# EC_mini_v31.net
KiCad netlist of a schematic drawn in EAGLE
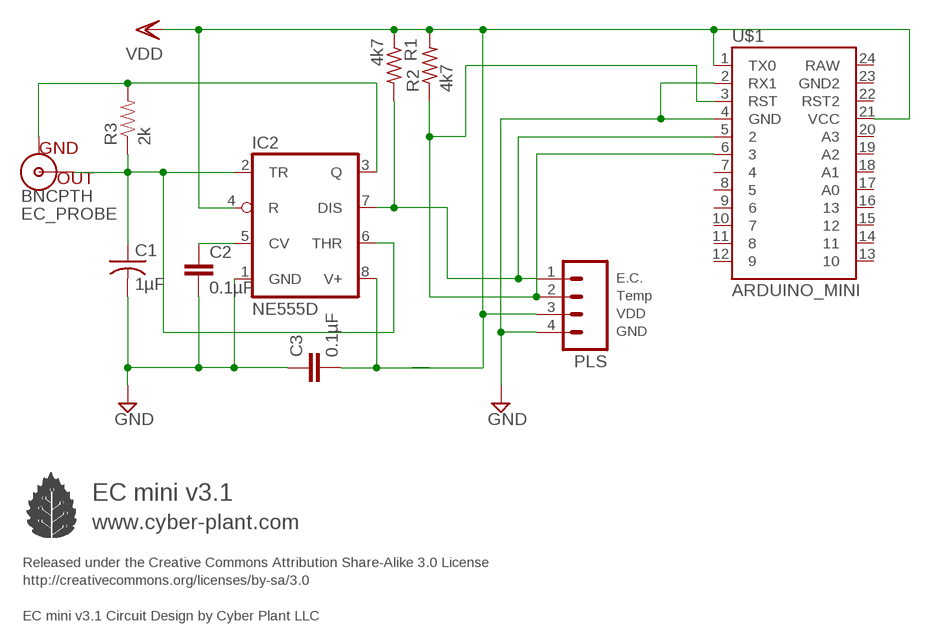
[diagram p0: schematic, sheet 1]

(export (version "E")
  (design (tool "Eeschema 10.0.6"))
  (components
    (comp (ref "C1")
      (value "1µF")
      (footprint "eagle-import:C050-045X075")
      (libsource (lib "eagle-import") (part "C-US050-045X075"))
    )
    (comp (ref "C2")
      (value "0.1µF")
      (footprint "eagle-import:1206")
      (libsource (lib "eagle-import") (part "CAP1206"))
    )
    (comp (ref "C3")
      (value "0.1µF")
      (footprint "eagle-import:1206")
      (libsource (lib "eagle-import") (part "CAP1206"))
    )
    (comp (ref "EC_PROBE")
      (value "BNCPTH")
      (footprint "eagle-import:BNC")
      (libsource (lib "eagle-import") (part "BNCPTH"))
    )
    (comp (ref "IC2")
      (value "NE555D")
      (footprint "eagle-import:SO08")
      (libsource (lib "eagle-import") (part "555DNE"))
    )
    (comp (ref "PLS")
      (value "M04PTH")
      (footprint "eagle-import:1X04")
      (libsource (lib "eagle-import") (part "M04PTH"))
    )
    (comp (ref "R1")
      (value "4k7")
      (footprint "eagle-import:0207_10")
      (libsource (lib "eagle-import") (part "R-US_0207/10"))
    )
    (comp (ref "R2")
      (value "4k7")
      (footprint "eagle-import:0207_10")
      (libsource (lib "eagle-import") (part "R-US_0207/10"))
    )
    (comp (ref "R3")
      (value "2k")
      (footprint "eagle-import:1206")
      (libsource (lib "eagle-import") (part "RESISTOR1206"))
    )
    (comp (ref "U$1")
      (value "ARDUINO_MINI")
      (footprint "eagle-import:ARDUINO_MINI")
      (libsource (lib "eagle-import") (part "ARDUINO_MINI"))
    )
  )
  (nets
    (net (code "1") (name "GND") (class "Default")
      (node (ref "C1") (pin "2") (pinfunction "2_2") (pintype "passive"))
      (node (ref "C2") (pin "2") (pinfunction "2_2") (pintype "passive"))
      (node (ref "C3") (pin "1") (pinfunction "1_1") (pintype "passive"))
      (node (ref "IC2") (pin "1") (pinfunction "GND_1") (pintype "power_in"))
      (node (ref "PLS") (pin "4") (pinfunction "4_4") (pintype "passive"))
      (node (ref "U$1") (pin "2") (pinfunction "RX1_2") (pintype "bidirectional"))
      (node (ref "U$1") (pin "4") (pinfunction "GND_4") (pintype "bidirectional"))
    )
    (net (code "2") (name "Net-(EC_PROBE-OUT)") (class "Default")
      (node (ref "C1") (pin "1") (pinfunction "1_1") (pintype "passive"))
      (node (ref "EC_PROBE") (pin "S") (pinfunction "OUT_S") (pintype "bidirectional"))
      (node (ref "IC2") (pin "2") (pinfunction "TR_2") (pintype "input"))
      (node (ref "IC2") (pin "6") (pinfunction "THR_6") (pintype "input"))
      (node (ref "R3") (pin "1") (pinfunction "1_1") (pintype "passive"))
    )
    (net (code "3") (name "Net-(IC2-CV)") (class "Default")
      (node (ref "C2") (pin "1") (pinfunction "1_1") (pintype "passive"))
      (node (ref "IC2") (pin "5") (pinfunction "CV_5") (pintype "input"))
    )
    (net (code "4") (name "Net-(IC2-DIS)") (class "Default")
      (node (ref "IC2") (pin "7") (pinfunction "DIS_7") (pintype "input"))
      (node (ref "PLS") (pin "1") (pinfunction "1_1") (pintype "passive"))
      (node (ref "R1") (pin "2") (pinfunction "2_2") (pintype "passive"))
      (node (ref "U$1") (pin "5") (pinfunction "2_5") (pintype "bidirectional"))
    )
    (net (code "5") (name "Net-(IC2-Q)") (class "Default")
      (node (ref "EC_PROBE") (pin "GND") (pinfunction "GND_GND") (pintype "bidirectional"))
      (node (ref "IC2") (pin "3") (pinfunction "Q_3") (pintype "output"))
      (node (ref "R3") (pin "2") (pinfunction "2_2") (pintype "passive"))
    )
    (net (code "6") (name "Net-(U$1-3)") (class "Default")
      (node (ref "PLS") (pin "2") (pinfunction "2_2") (pintype "passive"))
      (node (ref "R2") (pin "1") (pinfunction "1_1") (pintype "passive"))
      (node (ref "U$1") (pin "3") (pinfunction "RST_3") (pintype "bidirectional"))
      (node (ref "U$1") (pin "6") (pinfunction "3_6") (pintype "bidirectional"))
    )
    (net (code "7") (name "VDD") (class "Default")
      (node (ref "C3") (pin "2") (pinfunction "2_2") (pintype "passive"))
      (node (ref "IC2") (pin "4") (pinfunction "R_4") (pintype "input"))
      (node (ref "IC2") (pin "8") (pinfunction "V+_8") (pintype "power_in"))
      (node (ref "PLS") (pin "3") (pinfunction "3_3") (pintype "passive"))
      (node (ref "R1") (pin "1") (pinfunction "1_1") (pintype "passive"))
      (node (ref "R2") (pin "2") (pinfunction "2_2") (pintype "passive"))
      (node (ref "U$1") (pin "1") (pinfunction "TX0_1") (pintype "bidirectional"))
      (node (ref "U$1") (pin "21") (pinfunction "VCC_21") (pintype "bidirectional"))
    )
    (net (code "8") (name "unconnected-(U$1-4-Pad7)") (class "Default")
      (node (ref "U$1") (pin "7") (pinfunction "4_7") (pintype "bidirectional"))
    )
    (net (code "9") (name "unconnected-(U$1-5-Pad8)") (class "Default")
      (node (ref "U$1") (pin "8") (pinfunction "5_8") (pintype "bidirectional"))
    )
    (net (code "10") (name "unconnected-(U$1-6-Pad9)") (class "Default")
      (node (ref "U$1") (pin "9") (pinfunction "6_9") (pintype "bidirectional"))
    )
    (net (code "11") (name "unconnected-(U$1-7-Pad10)") (class "Default")
      (node (ref "U$1") (pin "10") (pinfunction "7_10") (pintype "bidirectional"))
    )
    (net (code "12") (name "unconnected-(U$1-8-Pad11)") (class "Default")
      (node (ref "U$1") (pin "11") (pinfunction "8_11") (pintype "bidirectional"))
    )
    (net (code "13") (name "unconnected-(U$1-9-Pad12)") (class "Default")
      (node (ref "U$1") (pin "12") (pinfunction "9_12") (pintype "bidirectional"))
    )
    (net (code "14") (name "unconnected-(U$1-10-Pad13)") (class "Default")
      (node (ref "U$1") (pin "13") (pinfunction "10_13") (pintype "bidirectional"))
    )
    (net (code "15") (name "unconnected-(U$1-11-Pad14)") (class "Default")
      (node (ref "U$1") (pin "14") (pinfunction "11_14") (pintype "bidirectional"))
    )
    (net (code "16") (name "unconnected-(U$1-12-Pad15)") (class "Default")
      (node (ref "U$1") (pin "15") (pinfunction "12_15") (pintype "bidirectional"))
    )
    (net (code "17") (name "unconnected-(U$1-13-Pad16)") (class "Default")
      (node (ref "U$1") (pin "16") (pinfunction "13_16") (pintype "bidirectional"))
    )
    (net (code "18") (name "unconnected-(U$1-A0-Pad17)") (class "Default")
      (node (ref "U$1") (pin "17") (pinfunction "A0_17") (pintype "bidirectional"))
    )
    (net (code "19") (name "unconnected-(U$1-A1-Pad18)") (class "Default")
      (node (ref "U$1") (pin "18") (pinfunction "A1_18") (pintype "bidirectional"))
    )
    (net (code "20") (name "unconnected-(U$1-A2-Pad19)") (class "Default")
      (node (ref "U$1") (pin "19") (pinfunction "A2_19") (pintype "bidirectional"))
    )
    (net (code "21") (name "unconnected-(U$1-A3-Pad20)") (class "Default")
      (node (ref "U$1") (pin "20") (pinfunction "A3_20") (pintype "bidirectional"))
    )
    (net (code "22") (name "unconnected-(U$1-GND2-Pad23)") (class "Default")
      (node (ref "U$1") (pin "23") (pinfunction "GND2_23") (pintype "bidirectional"))
    )
    (net (code "23") (name "unconnected-(U$1-RAW-Pad24)") (class "Default")
      (node (ref "U$1") (pin "24") (pinfunction "RAW_24") (pintype "bidirectional"))
    )
    (net (code "24") (name "unconnected-(U$1-RST2-Pad22)") (class "Default")
      (node (ref "U$1") (pin "22") (pinfunction "RST2_22") (pintype "bidirectional"))
    )
  )
)
